# MCU.net
KiCad netlist of a schematic drawn in Altium Designer
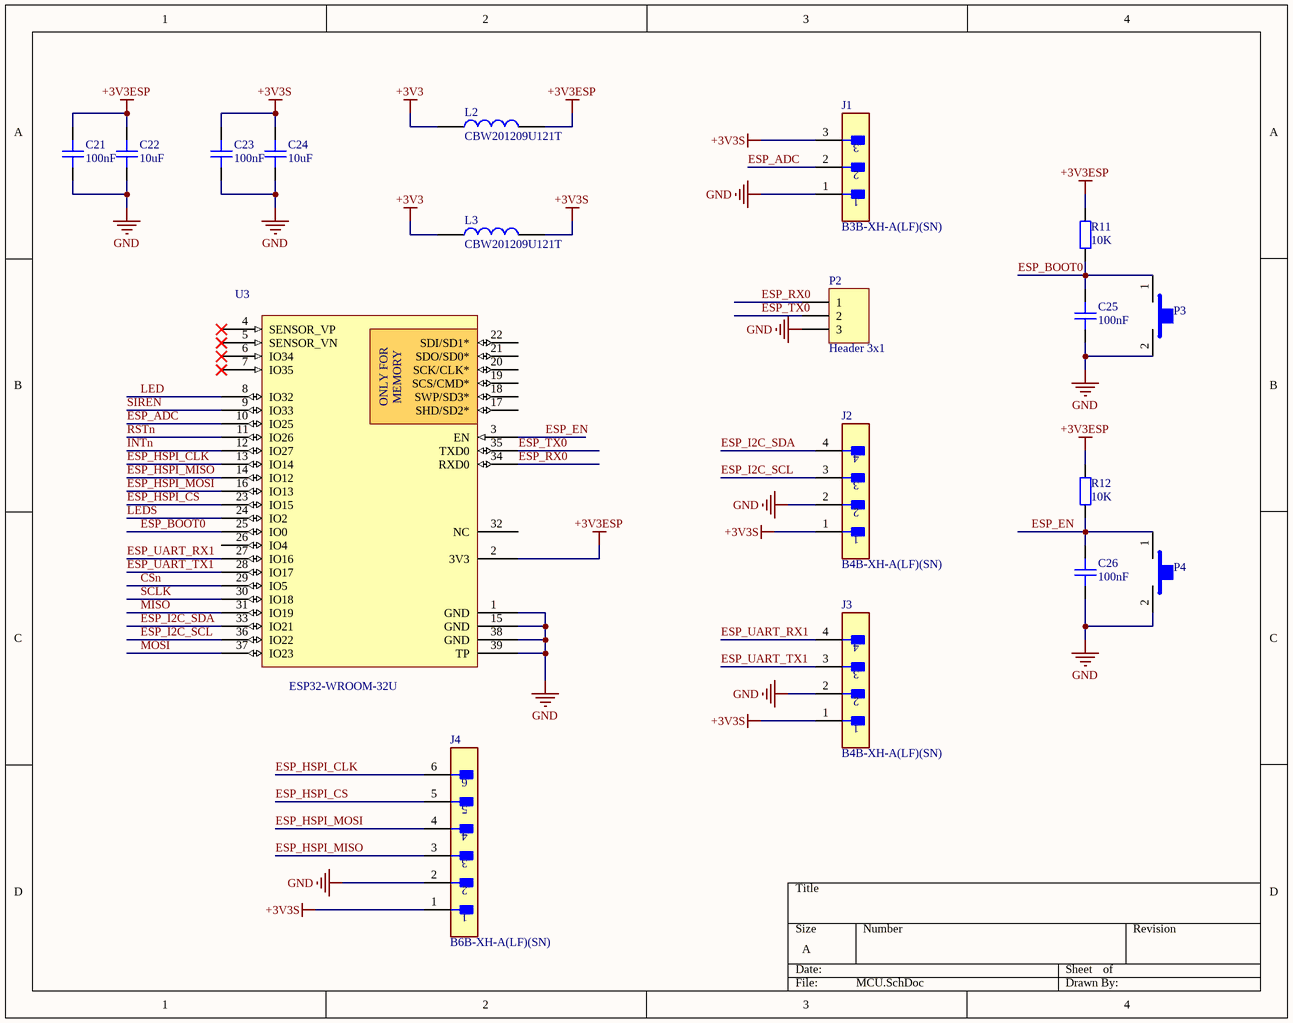
[diagram p0: MCU.SchDoc]

(export (version "E")
  (design (tool "Eeschema 10.0.6"))
  (components
    (comp (ref "C21")
      (value "100nF")
      (footprint "CAPC-0603 (1608)")
      (description "CAP CER 1uF 10% 16V X7R 0603")
      (fields (field (name "MPN") "CC0603KRX7R7BB105"))
      (libsource (lib "Integrated_Library_gateway_tbl") (part "CC0603KRX7R7BB105"))
    )
    (comp (ref "C22")
      (value "10uF")
      (footprint "CAPC-0603 (1608)")
      (description "CAP CER 0.018UF 50V X7R 0603")
      (fields (field (name "MPN") "CC0603JRX7R9BB183") (field (name "MFR") "Yageo"))
      (libsource (lib "Integrated_Library_gateway_tbl") (part "CC0603JRX7R9BB183"))
    )
    (comp (ref "C23")
      (value "100nF")
      (footprint "CAPC-0603 (1608)")
      (description "CAP CER 1uF 10% 16V X7R 0603")
      (fields (field (name "MPN") "CC0603KRX7R7BB105"))
      (libsource (lib "Integrated_Library_gateway_tbl") (part "CC0603KRX7R7BB105"))
    )
    (comp (ref "C24")
      (value "10uF")
      (footprint "CAPC-0603 (1608)")
      (description "CAP CER 0.018UF 50V X7R 0603")
      (fields (field (name "MPN") "CC0603JRX7R9BB183") (field (name "MFR") "Yageo"))
      (libsource (lib "Integrated_Library_gateway_tbl") (part "CC0603JRX7R9BB183"))
    )
    (comp (ref "C25")
      (value "100nF")
      (footprint "CAPC-0603 (1608)")
      (description "CAP CER 0.22UF 50V Y5V 0603")
      (fields (field (name "MPN") "CC0603ZRY5V9BB224"))
      (libsource (lib "Integrated_Library_gateway_tbl") (part "CC0603ZRY5V9BB224"))
    )
    (comp (ref "C26")
      (value "100nF")
      (footprint "CAPC-0603 (1608)")
      (description "CAP CER 0.22UF 50V Y5V 0603")
      (fields (field (name "MPN") "CC0603ZRY5V9BB224"))
      (libsource (lib "Integrated_Library_gateway_tbl") (part "CC0603ZRY5V9BB224"))
    )
    (comp (ref "J1")
      (value "B3B-XH-A(LF)(SN)")
      (footprint "FP-B3B-XH-A_LF_SN-MFG")
      (description "CONN HEADER VERT 3POS 2.5MM")
      (libsource (lib "Altium Content Vault") (part "0d3f023dd272f625e17a2be33dea85f"))
    )
    (comp (ref "J2")
      (value "B4B-XH-A(LF)(SN)")
      (footprint "FP-B4B-XH-A_LF_SN-MFG")
      (description "CONN HEADER VERT 4POS 2.5MM")
      (libsource (lib "Altium Content Vault") (part "299a8cea1bdcbc3624fe62c390fa72c"))
    )
    (comp (ref "J3")
      (value "B4B-XH-A(LF)(SN)")
      (footprint "FP-B4B-XH-A_LF_SN-MFG")
      (description "CONN HEADER VERT 4POS 2.5MM")
      (libsource (lib "Altium Content Vault") (part "299a8cea1bdcbc3624fe62c390fa72c"))
    )
    (comp (ref "J4")
      (value "B6B-XH-A(LF)(SN)")
      (footprint "FP-B6B-XH-A_LF_SN-MFG")
      (description "CONN HEADER VERT 6POS 2.5MM")
      (libsource (lib "Altium Content Vault") (part "f2cb566baf1c37ab5a3b8e90bbeafd6"))
    )
    (comp (ref "L2")
      (value "CBW201209U121T")
      (footprint "IND-0805 (2012)")
      (description "IND-FERRITE BEAD 220 OHM 0805 1LN")
      (fields (field (name "MPN") "MPZ2012S221A"))
      (libsource (lib "Integrated_Library_gateway_tbl") (part "MPZ2012S221A"))
    )
    (comp (ref "L3")
      (value "CBW201209U121T")
      (footprint "IND-0805 (2012)")
      (description "IND-FERRITE BEAD 220 OHM 0805 1LN")
      (fields (field (name "MPN") "MPZ2012S221A"))
      (libsource (lib "Integrated_Library_gateway_tbl") (part "MPZ2012S221A"))
    )
    (comp (ref "P2")
      (value "Header 3x1")
      (footprint "HDR1X3")
      (description "Header, 3-Pin, pitch 2.54mm")
      (libsource (lib "Integrated_Library_gateway_tbl") (part "Header 3x1"))
    )
    (comp (ref "P3")
      (value "~")
      (footprint "SW 2P SMD")
      (description "SMD Mini Push Button Switch 2 Pin 3x6x2.7mm")
      (fields (field (name "MPN") "SMD Mini Push Button 2 SMD"))
      (libsource (lib "Integrated_Library_gateway_tbl") (part "Button 2 SMD"))
    )
    (comp (ref "P4")
      (value "~")
      (footprint "SW 2P SMD")
      (description "SMD Mini Push Button Switch 2 Pin 3x6x2.7mm")
      (fields (field (name "MPN") "SMD Mini Push Button 2 SMD"))
      (libsource (lib "Integrated_Library_gateway_tbl") (part "Button 2 SMD"))
    )
    (comp (ref "R11")
      (value "10K")
      (footprint "RESC-0603 (1608)")
      (description "RES SMD 10K OHM 1% 1/10W 0603")
      (fields (field (name "MPN") "RC0603FR-0710KL"))
      (libsource (lib "Integrated_Library_gateway_tbl") (part "RC0603FR-0710KL"))
    )
    (comp (ref "R12")
      (value "10K")
      (footprint "RESC-0603 (1608)")
      (description "RES SMD 10K OHM 1% 1/10W 0603")
      (fields (field (name "MPN") "RC0603FR-0710KL"))
      (libsource (lib "Integrated_Library_gateway_tbl") (part "RC0603FR-0710KL"))
    )
    (comp (ref "U3")
      (value "ESP32-WROOM-32U")
      (footprint "ESP32-WROOM-32U")
      (description "Wi-Fi/BT BLE Module ESP32-D0WD")
      (fields (field (name "MFR") "Espressif"))
      (libsource (lib "Integrated_Library_gateway_tbl") (part "ESP32-WROOM-32U"))
    )
  )
  (nets
    (net (code "1") (name "+3V3") (class "Default")
      (node (ref "L2") (pin "2") (pinfunction "2_2") (pintype "passive"))
      (node (ref "L3") (pin "2") (pinfunction "2_2") (pintype "passive"))
    )
    (net (code "2") (name "+3V3ESP") (class "Default")
      (node (ref "C21") (pin "2") (pinfunction "2_2") (pintype "passive"))
      (node (ref "C22") (pin "2") (pinfunction "2_2") (pintype "passive"))
      (node (ref "L2") (pin "1") (pinfunction "1_1") (pintype "passive"))
      (node (ref "R11") (pin "2") (pinfunction "2_2") (pintype "passive"))
      (node (ref "R12") (pin "2") (pinfunction "2_2") (pintype "passive"))
      (node (ref "U3") (pin "2") (pinfunction "3V3_2") (pintype "power_in"))
    )
    (net (code "3") (name "+3V3S") (class "Default")
      (node (ref "C23") (pin "2") (pinfunction "2_2") (pintype "passive"))
      (node (ref "C24") (pin "2") (pinfunction "2_2") (pintype "passive"))
      (node (ref "J1") (pin "3") (pinfunction "3_3") (pintype "passive"))
      (node (ref "J2") (pin "1") (pinfunction "1_1") (pintype "passive"))
      (node (ref "J3") (pin "1") (pinfunction "1_1") (pintype "passive"))
      (node (ref "J4") (pin "1") (pinfunction "1_1") (pintype "passive"))
      (node (ref "L3") (pin "1") (pinfunction "1_1") (pintype "passive"))
    )
    (net (code "4") (name "/CSn") (class "Default")
      (node (ref "U3") (pin "29") (pinfunction "IO5_29") (pintype "bidirectional"))
    )
    (net (code "5") (name "/ESP_ADC") (class "Default")
      (node (ref "J1") (pin "2") (pinfunction "2_2") (pintype "passive"))
      (node (ref "U3") (pin "10") (pinfunction "IO25_10") (pintype "bidirectional"))
    )
    (net (code "6") (name "/ESP_BOOT0") (class "Default")
      (node (ref "C25") (pin "2") (pinfunction "2_2") (pintype "passive"))
      (node (ref "P3") (pin "1") (pinfunction "1_1") (pintype "passive"))
      (node (ref "R11") (pin "1") (pinfunction "1_1") (pintype "passive"))
      (node (ref "U3") (pin "25") (pinfunction "IO0_25") (pintype "bidirectional"))
    )
    (net (code "7") (name "/ESP_EN") (class "Default")
      (node (ref "C26") (pin "2") (pinfunction "2_2") (pintype "passive"))
      (node (ref "P4") (pin "1") (pinfunction "1_1") (pintype "passive"))
      (node (ref "R12") (pin "1") (pinfunction "1_1") (pintype "passive"))
      (node (ref "U3") (pin "3") (pinfunction "EN_3") (pintype "input"))
    )
    (net (code "8") (name "/ESP_HSPI_CLK") (class "Default")
      (node (ref "J4") (pin "6") (pinfunction "6_6") (pintype "passive"))
      (node (ref "U3") (pin "13") (pinfunction "IO14_13") (pintype "bidirectional"))
    )
    (net (code "9") (name "/ESP_HSPI_CS") (class "Default")
      (node (ref "J4") (pin "5") (pinfunction "5_5") (pintype "passive"))
      (node (ref "U3") (pin "23") (pinfunction "IO15_23") (pintype "bidirectional"))
    )
    (net (code "10") (name "/ESP_HSPI_MISO") (class "Default")
      (node (ref "J4") (pin "3") (pinfunction "3_3") (pintype "passive"))
      (node (ref "U3") (pin "14") (pinfunction "IO12_14") (pintype "bidirectional"))
    )
    (net (code "11") (name "/ESP_HSPI_MOSI") (class "Default")
      (node (ref "J4") (pin "4") (pinfunction "4_4") (pintype "passive"))
      (node (ref "U3") (pin "16") (pinfunction "IO13_16") (pintype "bidirectional"))
    )
    (net (code "12") (name "/ESP_I2C_SCL") (class "Default")
      (node (ref "J2") (pin "3") (pinfunction "3_3") (pintype "passive"))
      (node (ref "U3") (pin "36") (pinfunction "IO22_36") (pintype "bidirectional"))
    )
    (net (code "13") (name "/ESP_I2C_SDA") (class "Default")
      (node (ref "J2") (pin "4") (pinfunction "4_4") (pintype "passive"))
      (node (ref "U3") (pin "33") (pinfunction "IO21_33") (pintype "bidirectional"))
    )
    (net (code "14") (name "/ESP_RX0") (class "Default")
      (node (ref "P2") (pin "1") (pinfunction "1_1") (pintype "passive"))
      (node (ref "U3") (pin "34") (pinfunction "RXD0_34") (pintype "bidirectional"))
    )
    (net (code "15") (name "/ESP_TX0") (class "Default")
      (node (ref "P2") (pin "2") (pinfunction "2_2") (pintype "passive"))
      (node (ref "U3") (pin "35") (pinfunction "TXD0_35") (pintype "bidirectional"))
    )
    (net (code "16") (name "/ESP_UART_RX1") (class "Default")
      (node (ref "J3") (pin "4") (pinfunction "4_4") (pintype "passive"))
      (node (ref "U3") (pin "27") (pinfunction "IO16_27") (pintype "bidirectional"))
    )
    (net (code "17") (name "/ESP_UART_TX1") (class "Default")
      (node (ref "J3") (pin "3") (pinfunction "3_3") (pintype "passive"))
      (node (ref "U3") (pin "28") (pinfunction "IO17_28") (pintype "bidirectional"))
    )
    (net (code "18") (name "/INTn") (class "Default")
      (node (ref "U3") (pin "12") (pinfunction "IO27_12") (pintype "bidirectional"))
    )
    (net (code "19") (name "/LED") (class "Default")
      (node (ref "U3") (pin "8") (pinfunction "IO32_8") (pintype "bidirectional"))
    )
    (net (code "20") (name "/LEDS") (class "Default")
      (node (ref "U3") (pin "24") (pinfunction "IO2_24") (pintype "bidirectional"))
    )
    (net (code "21") (name "/MISO") (class "Default")
      (node (ref "U3") (pin "31") (pinfunction "IO19_31") (pintype "bidirectional"))
    )
    (net (code "22") (name "/MOSI") (class "Default")
      (node (ref "U3") (pin "37") (pinfunction "IO23_37") (pintype "bidirectional"))
    )
    (net (code "23") (name "/RSTn") (class "Default")
      (node (ref "U3") (pin "11") (pinfunction "IO26_11") (pintype "bidirectional"))
    )
    (net (code "24") (name "/SCLK") (class "Default")
      (node (ref "U3") (pin "30") (pinfunction "IO18_30") (pintype "bidirectional"))
    )
    (net (code "25") (name "/SIREN") (class "Default")
      (node (ref "U3") (pin "9") (pinfunction "IO33_9") (pintype "bidirectional"))
    )
    (net (code "26") (name "GND") (class "Default")
      (node (ref "C21") (pin "1") (pinfunction "1_1") (pintype "passive"))
      (node (ref "C22") (pin "1") (pinfunction "1_1") (pintype "passive"))
      (node (ref "C23") (pin "1") (pinfunction "1_1") (pintype "passive"))
      (node (ref "C24") (pin "1") (pinfunction "1_1") (pintype "passive"))
      (node (ref "C25") (pin "1") (pinfunction "1_1") (pintype "passive"))
      (node (ref "C26") (pin "1") (pinfunction "1_1") (pintype "passive"))
      (node (ref "J1") (pin "1") (pinfunction "1_1") (pintype "passive"))
      (node (ref "J2") (pin "2") (pinfunction "2_2") (pintype "passive"))
      (node (ref "J3") (pin "2") (pinfunction "2_2") (pintype "passive"))
      (node (ref "J4") (pin "2") (pinfunction "2_2") (pintype "passive"))
      (node (ref "P2") (pin "3") (pinfunction "3_3") (pintype "passive"))
      (node (ref "P3") (pin "2") (pinfunction "2_2") (pintype "passive"))
      (node (ref "P4") (pin "2") (pinfunction "2_2") (pintype "passive"))
      (node (ref "U3") (pin "1") (pinfunction "GND_1") (pintype "power_in"))
      (node (ref "U3") (pin "15") (pinfunction "GND_15") (pintype "power_in"))
      (node (ref "U3") (pin "38") (pinfunction "GND_38") (pintype "power_in"))
      (node (ref "U3") (pin "39") (pinfunction "TP_39") (pintype "power_in"))
    )
    (net (code "27") (name "unconnected-(U3-IO4-Pad26)") (class "Default")
      (node (ref "U3") (pin "26") (pinfunction "IO4_26") (pintype "bidirectional"))
    )
    (net (code "28") (name "unconnected-(U3-IO34-Pad6)") (class "Default")
      (node (ref "U3") (pin "6") (pinfunction "IO34_6") (pintype "input+no_connect"))
    )
    (net (code "29") (name "unconnected-(U3-IO35-Pad7)") (class "Default")
      (node (ref "U3") (pin "7") (pinfunction "IO35_7") (pintype "input+no_connect"))
    )
    (net (code "30") (name "unconnected-(U3-NC-Pad32)") (class "Default")
      (node (ref "U3") (pin "32") (pinfunction "NC_32") (pintype "passive"))
    )
    (net (code "31") (name "unconnected-(U3-SCK{slash}CLK*-Pad20)") (class "Default")
      (node (ref "U3") (pin "20") (pinfunction "SCK/CLK*_20") (pintype "bidirectional"))
    )
    (net (code "32") (name "unconnected-(U3-SCS{slash}CMD*-Pad19)") (class "Default")
      (node (ref "U3") (pin "19") (pinfunction "SCS/CMD*_19") (pintype "bidirectional"))
    )
    (net (code "33") (name "unconnected-(U3-SDI{slash}SD1*-Pad22)") (class "Default")
      (node (ref "U3") (pin "22") (pinfunction "SDI/SD1*_22") (pintype "bidirectional"))
    )
    (net (code "34") (name "unconnected-(U3-SDO{slash}SD0*-Pad21)") (class "Default")
      (node (ref "U3") (pin "21") (pinfunction "SDO/SD0*_21") (pintype "bidirectional"))
    )
    (net (code "35") (name "unconnected-(U3-SENSOR_VN-Pad5)") (class "Default")
      (node (ref "U3") (pin "5") (pinfunction "SENSOR_VN_5") (pintype "input+no_connect"))
    )
    (net (code "36") (name "unconnected-(U3-SENSOR_VP-Pad4)") (class "Default")
      (node (ref "U3") (pin "4") (pinfunction "SENSOR_VP_4") (pintype "input+no_connect"))
    )
    (net (code "37") (name "unconnected-(U3-SHD{slash}SD2*-Pad17)") (class "Default")
      (node (ref "U3") (pin "17") (pinfunction "SHD/SD2*_17") (pintype "bidirectional"))
    )
    (net (code "38") (name "unconnected-(U3-SWP{slash}SD3*-Pad18)") (class "Default")
      (node (ref "U3") (pin "18") (pinfunction "SWP/SD3*_18") (pintype "bidirectional"))
    )
  )
)
